# POWER_SWITCH.net
KiCad netlist of a schematic drawn in Altium Designer
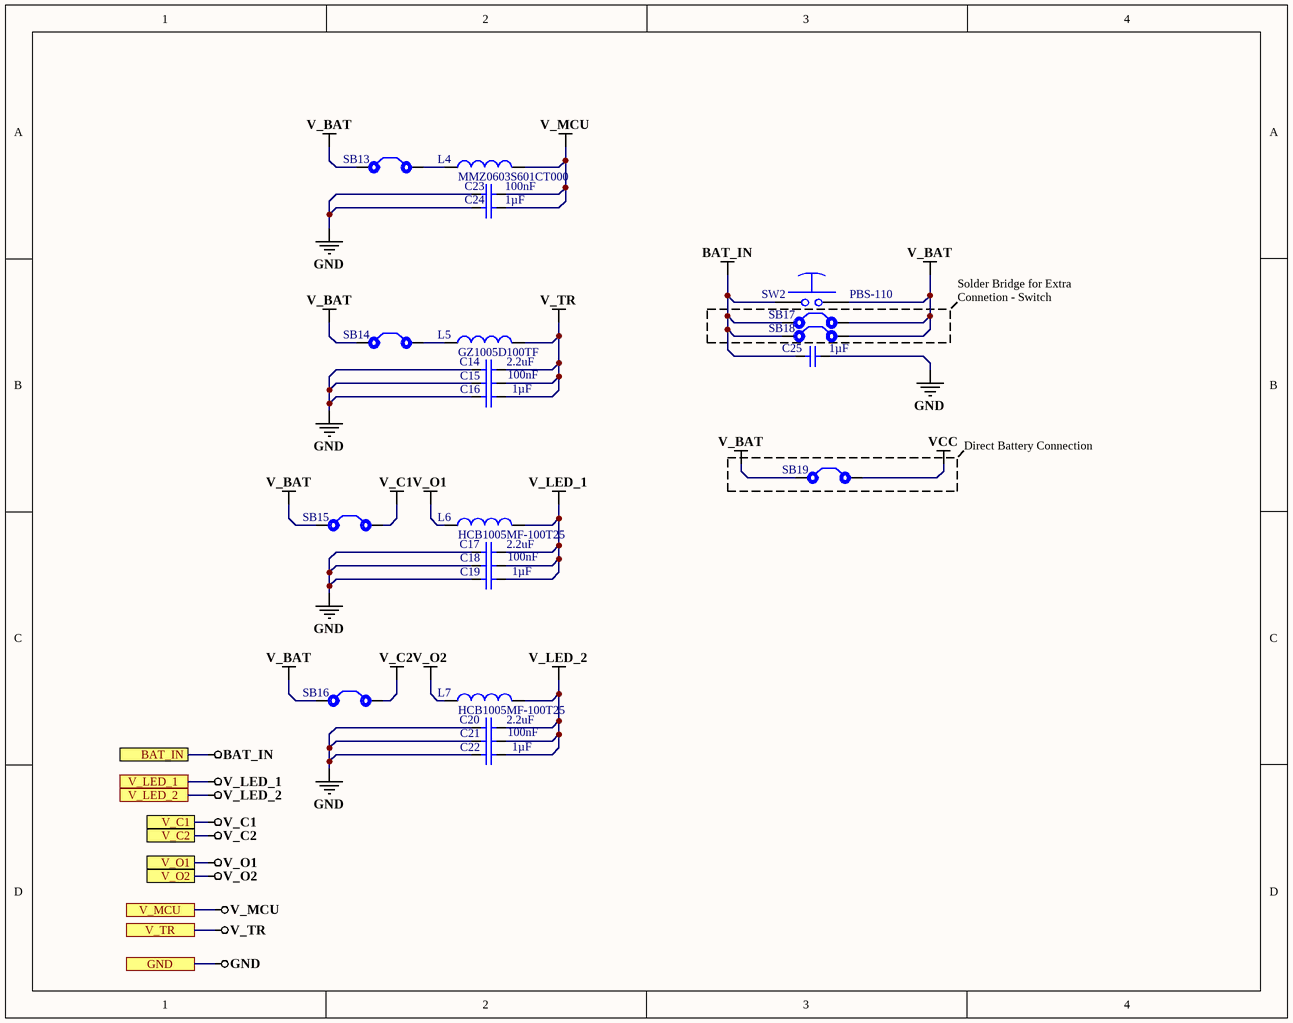
[diagram p0: POWER_SWITCH.SchDoc]

(export (version "E")
  (design (tool "Eeschema 10.0.6"))
  (components
    (comp (ref "C14")
      (value "2.2uF")
      (footprint "Cap0402")
      (description "CAP CER 2.2UF 25V X5R 0402")
      (fields
        (field (name "MANUFACTURER") "Samsung")
        (field (name "MANUFACTURER PART NUMBER") "CL05A225KA5NUNC")
      )
      (libsource (lib "TT_IntLib") (part "CL05A225KA5NUNC"))
    )
    (comp (ref "C15")
      (value "100nF")
      (footprint "Cap0402")
      (description "CAP CER 0.1UF 25V X7R 0402")
      (fields
        (field (name "MANUFACTURER") "Yageo")
        (field (name "MANUFACTURER PART NUMBER") "CC0402KRX7R8BB104")
      )
      (libsource (lib "TT_IntLib") (part "CC0402KRX7R8BB104"))
    )
    (comp (ref "C16")
      (value "1µF")
      (footprint "Cap0402")
      (description "CAP CER 1UF 25V X5R 0402")
      (fields
        (field (name "MANUFACTURER") "Murata")
        (field (name "MANUFACTURER PART NUMBER") "GRM155R61E105KA12D")
      )
      (libsource (lib "TT_IntLib") (part "GRM155R61E105KA12D"))
    )
    (comp (ref "C17")
      (value "2.2uF")
      (footprint "Cap0402")
      (description "CAP CER 2.2UF 25V X5R 0402")
      (fields
        (field (name "MANUFACTURER") "Samsung")
        (field (name "MANUFACTURER PART NUMBER") "CL05A225KA5NUNC")
      )
      (libsource (lib "TT_IntLib") (part "CL05A225KA5NUNC"))
    )
    (comp (ref "C18")
      (value "100nF")
      (footprint "Cap0402")
      (description "CAP CER 0.1UF 25V X7R 0402")
      (fields
        (field (name "MANUFACTURER") "Yageo")
        (field (name "MANUFACTURER PART NUMBER") "CC0402KRX7R8BB104")
      )
      (libsource (lib "TT_IntLib") (part "CC0402KRX7R8BB104"))
    )
    (comp (ref "C19")
      (value "1µF")
      (footprint "Cap0402")
      (description "CAP CER 1UF 25V X5R 0402")
      (fields
        (field (name "MANUFACTURER") "Murata")
        (field (name "MANUFACTURER PART NUMBER") "GRM155R61E105KA12D")
      )
      (libsource (lib "TT_IntLib") (part "GRM155R61E105KA12D"))
    )
    (comp (ref "C20")
      (value "2.2uF")
      (footprint "Cap0402")
      (description "CAP CER 2.2UF 25V X5R 0402")
      (fields
        (field (name "MANUFACTURER") "Samsung")
        (field (name "MANUFACTURER PART NUMBER") "CL05A225KA5NUNC")
      )
      (libsource (lib "TT_IntLib") (part "CL05A225KA5NUNC"))
    )
    (comp (ref "C21")
      (value "100nF")
      (footprint "Cap0402")
      (description "CAP CER 0.1UF 25V X7R 0402")
      (fields
        (field (name "MANUFACTURER") "Yageo")
        (field (name "MANUFACTURER PART NUMBER") "CC0402KRX7R8BB104")
      )
      (libsource (lib "TT_IntLib") (part "CC0402KRX7R8BB104"))
    )
    (comp (ref "C22")
      (value "1µF")
      (footprint "Cap0402")
      (description "CAP CER 1UF 25V X5R 0402")
      (fields
        (field (name "MANUFACTURER") "Murata")
        (field (name "MANUFACTURER PART NUMBER") "GRM155R61E105KA12D")
      )
      (libsource (lib "TT_IntLib") (part "GRM155R61E105KA12D"))
    )
    (comp (ref "C23")
      (value "100nF")
      (footprint "Cap0402")
      (description "CAP CER 0.1UF 25V X7R 0402")
      (fields
        (field (name "MANUFACTURER") "Yageo")
        (field (name "MANUFACTURER PART NUMBER") "CC0402KRX7R8BB104")
      )
      (libsource (lib "TT_IntLib") (part "CC0402KRX7R8BB104"))
    )
    (comp (ref "C24")
      (value "1µF")
      (footprint "Cap0402")
      (description "CAP CER 1UF 25V X5R 0402")
      (fields
        (field (name "MANUFACTURER") "Murata")
        (field (name "MANUFACTURER PART NUMBER") "GRM155R61E105KA12D")
      )
      (libsource (lib "TT_IntLib") (part "GRM155R61E105KA12D"))
    )
    (comp (ref "C25")
      (value "1µF")
      (footprint "Cap0402")
      (description "CAP CER 1UF 25V X5R 0402")
      (fields
        (field (name "MANUFACTURER") "Murata")
        (field (name "MANUFACTURER PART NUMBER") "GRM155R61E105KA12D")
      )
      (libsource (lib "TT_IntLib") (part "GRM155R61E105KA12D"))
    )
    (comp (ref "L4")
      (value "MMZ0603S601CT000")
      (footprint "IND 0201")
      (description "FERRITE BEAD 600 OHM 0201 1LN")
      (fields (field (name "MANUFACTURER") "TDK") (field (name "TOLERANCE") "25%"))
      (libsource (lib "TT_IntLib") (part "MMZ0603S601CT000"))
    )
    (comp (ref "L5")
      (value "GZ1005D100TF")
      (footprint "IND 0402 (1005 Metric)")
      (description "10Ω 100MHz 500mA 1 50mΩ 0402 Ferrite Beads")
      (fields (field (name "MANUFACTURER") "Sunlord"))
      (libsource (lib "TT_IntLib") (part "GZ1005D100TF"))
    )
    (comp (ref "L6")
      (value "HCB1005MF-100T25")
      (footprint "HCB1005MF-100T25")
      (description "10Ω 100MHz 2.5A 1 50mΩ 0402 Ferrite Beads")
      (fields (field (name "MANUFACTURER") "TAI-TECH"))
      (libsource (lib "TT_IntLib") (part "HCB1005MF-100T25"))
    )
    (comp (ref "L7")
      (value "HCB1005MF-100T25")
      (footprint "HCB1005MF-100T25")
      (description "10Ω 100MHz 2.5A 1 50mΩ 0402 Ferrite Beads")
      (fields (field (name "MANUFACTURER") "TAI-TECH"))
      (libsource (lib "TT_IntLib") (part "HCB1005MF-100T25"))
    )
    (comp (ref "SB13")
      (value "Solder Bridge")
      (footprint "Solder Bridge")
      (description "Solder Bridge ON")
      (libsource (lib "TT_IntLib") (part "Solder Bridge"))
    )
    (comp (ref "SB14")
      (value "Solder Bridge")
      (footprint "Solder Bridge")
      (description "Solder Bridge ON")
      (libsource (lib "TT_IntLib") (part "Solder Bridge"))
    )
    (comp (ref "SB15")
      (value "Solder Bridge")
      (footprint "Solder Bridge")
      (description "Solder Bridge ON")
      (libsource (lib "TT_IntLib") (part "Solder Bridge"))
    )
    (comp (ref "SB16")
      (value "Solder Bridge")
      (footprint "Solder Bridge")
      (description "Solder Bridge ON")
      (libsource (lib "TT_IntLib") (part "Solder Bridge"))
    )
    (comp (ref "SB17")
      (value "Solder Bridge")
      (footprint "Solder Bridge")
      (description "Solder Bridge ON")
      (libsource (lib "TT_IntLib") (part "Solder Bridge"))
    )
    (comp (ref "SB18")
      (value "Solder Bridge")
      (footprint "Solder Bridge")
      (description "Solder Bridge ON")
      (libsource (lib "TT_IntLib") (part "Solder Bridge"))
    )
    (comp (ref "SB19")
      (value "Solder Bridge")
      (footprint "Solder Bridge")
      (description "Solder Bridge ON")
      (libsource (lib "TT_IntLib") (part "Solder Bridge"))
    )
    (comp (ref "SW2")
      (value "PBS-110")
      (footprint "PBS-110")
      (description "Conn Isolated Power Socket Strip SKT 20 POS 4.19mm Solder ST Thru-Hole 20 Terminal 1 Port Tube")
      (libsource (lib "TT_IntLib") (part "PBS-110"))
    )
  )
  (nets
    (net (code "1") (name "BAT_IN") (class "Default")
      (node (ref "C25") (pin "2") (pintype "passive"))
      (node (ref "SB17") (pin "1") (pinfunction "1_1") (pintype "passive"))
      (node (ref "SB18") (pin "1") (pinfunction "1_1") (pintype "passive"))
      (node (ref "SW2") (pin "1") (pintype "passive"))
    )
    (net (code "2") (name "GND") (class "Default")
      (node (ref "C14") (pin "2") (pintype "passive"))
      (node (ref "C15") (pin "2") (pintype "passive"))
      (node (ref "C16") (pin "2") (pintype "passive"))
      (node (ref "C17") (pin "2") (pintype "passive"))
      (node (ref "C18") (pin "2") (pintype "passive"))
      (node (ref "C19") (pin "2") (pintype "passive"))
      (node (ref "C20") (pin "2") (pintype "passive"))
      (node (ref "C21") (pin "2") (pintype "passive"))
      (node (ref "C22") (pin "2") (pintype "passive"))
      (node (ref "C23") (pin "2") (pintype "passive"))
      (node (ref "C24") (pin "2") (pintype "passive"))
      (node (ref "C25") (pin "1") (pintype "passive"))
    )
    (net (code "3") (name "Net-(L4-Pad1)") (class "Default")
      (node (ref "L4") (pin "1") (pinfunction "1_1") (pintype "passive"))
      (node (ref "SB13") (pin "2") (pinfunction "2_2") (pintype "passive"))
    )
    (net (code "4") (name "Net-(L5-Pad1)") (class "Default")
      (node (ref "L5") (pin "1") (pinfunction "1_1") (pintype "passive"))
      (node (ref "SB14") (pin "2") (pinfunction "2_2") (pintype "passive"))
    )
    (net (code "5") (name "VCC") (class "Default")
      (node (ref "SB19") (pin "2") (pinfunction "2_2") (pintype "passive"))
    )
    (net (code "6") (name "V_BAT") (class "Default")
      (node (ref "SB13") (pin "1") (pinfunction "1_1") (pintype "passive"))
      (node (ref "SB14") (pin "1") (pinfunction "1_1") (pintype "passive"))
      (node (ref "SB15") (pin "1") (pinfunction "1_1") (pintype "passive"))
      (node (ref "SB16") (pin "1") (pinfunction "1_1") (pintype "passive"))
      (node (ref "SB17") (pin "2") (pinfunction "2_2") (pintype "passive"))
      (node (ref "SB18") (pin "2") (pinfunction "2_2") (pintype "passive"))
      (node (ref "SB19") (pin "1") (pinfunction "1_1") (pintype "passive"))
      (node (ref "SW2") (pin "2") (pintype "passive"))
    )
    (net (code "7") (name "V_C1") (class "Default")
      (node (ref "SB15") (pin "2") (pinfunction "2_2") (pintype "passive"))
    )
    (net (code "8") (name "V_C2") (class "Default")
      (node (ref "SB16") (pin "2") (pinfunction "2_2") (pintype "passive"))
    )
    (net (code "9") (name "V_LED_1") (class "Default")
      (node (ref "C17") (pin "1") (pintype "passive"))
      (node (ref "C18") (pin "1") (pintype "passive"))
      (node (ref "C19") (pin "1") (pintype "passive"))
      (node (ref "L6") (pin "2") (pinfunction "2_2") (pintype "passive"))
    )
    (net (code "10") (name "V_LED_2") (class "Default")
      (node (ref "C20") (pin "1") (pintype "passive"))
      (node (ref "C21") (pin "1") (pintype "passive"))
      (node (ref "C22") (pin "1") (pintype "passive"))
      (node (ref "L7") (pin "2") (pinfunction "2_2") (pintype "passive"))
    )
    (net (code "11") (name "V_MCU") (class "Default")
      (node (ref "C23") (pin "1") (pintype "passive"))
      (node (ref "C24") (pin "1") (pintype "passive"))
      (node (ref "L4") (pin "2") (pinfunction "2_2") (pintype "passive"))
    )
    (net (code "12") (name "V_O1") (class "Default")
      (node (ref "L6") (pin "1") (pinfunction "1_1") (pintype "passive"))
    )
    (net (code "13") (name "V_O2") (class "Default")
      (node (ref "L7") (pin "1") (pinfunction "1_1") (pintype "passive"))
    )
    (net (code "14") (name "V_TR") (class "Default")
      (node (ref "C14") (pin "1") (pintype "passive"))
      (node (ref "C15") (pin "1") (pintype "passive"))
      (node (ref "C16") (pin "1") (pintype "passive"))
      (node (ref "L5") (pin "2") (pinfunction "2_2") (pintype "passive"))
    )
  )
)
